# top_3-28-21.net
KiCad netlist of a schematic drawn in EAGLE
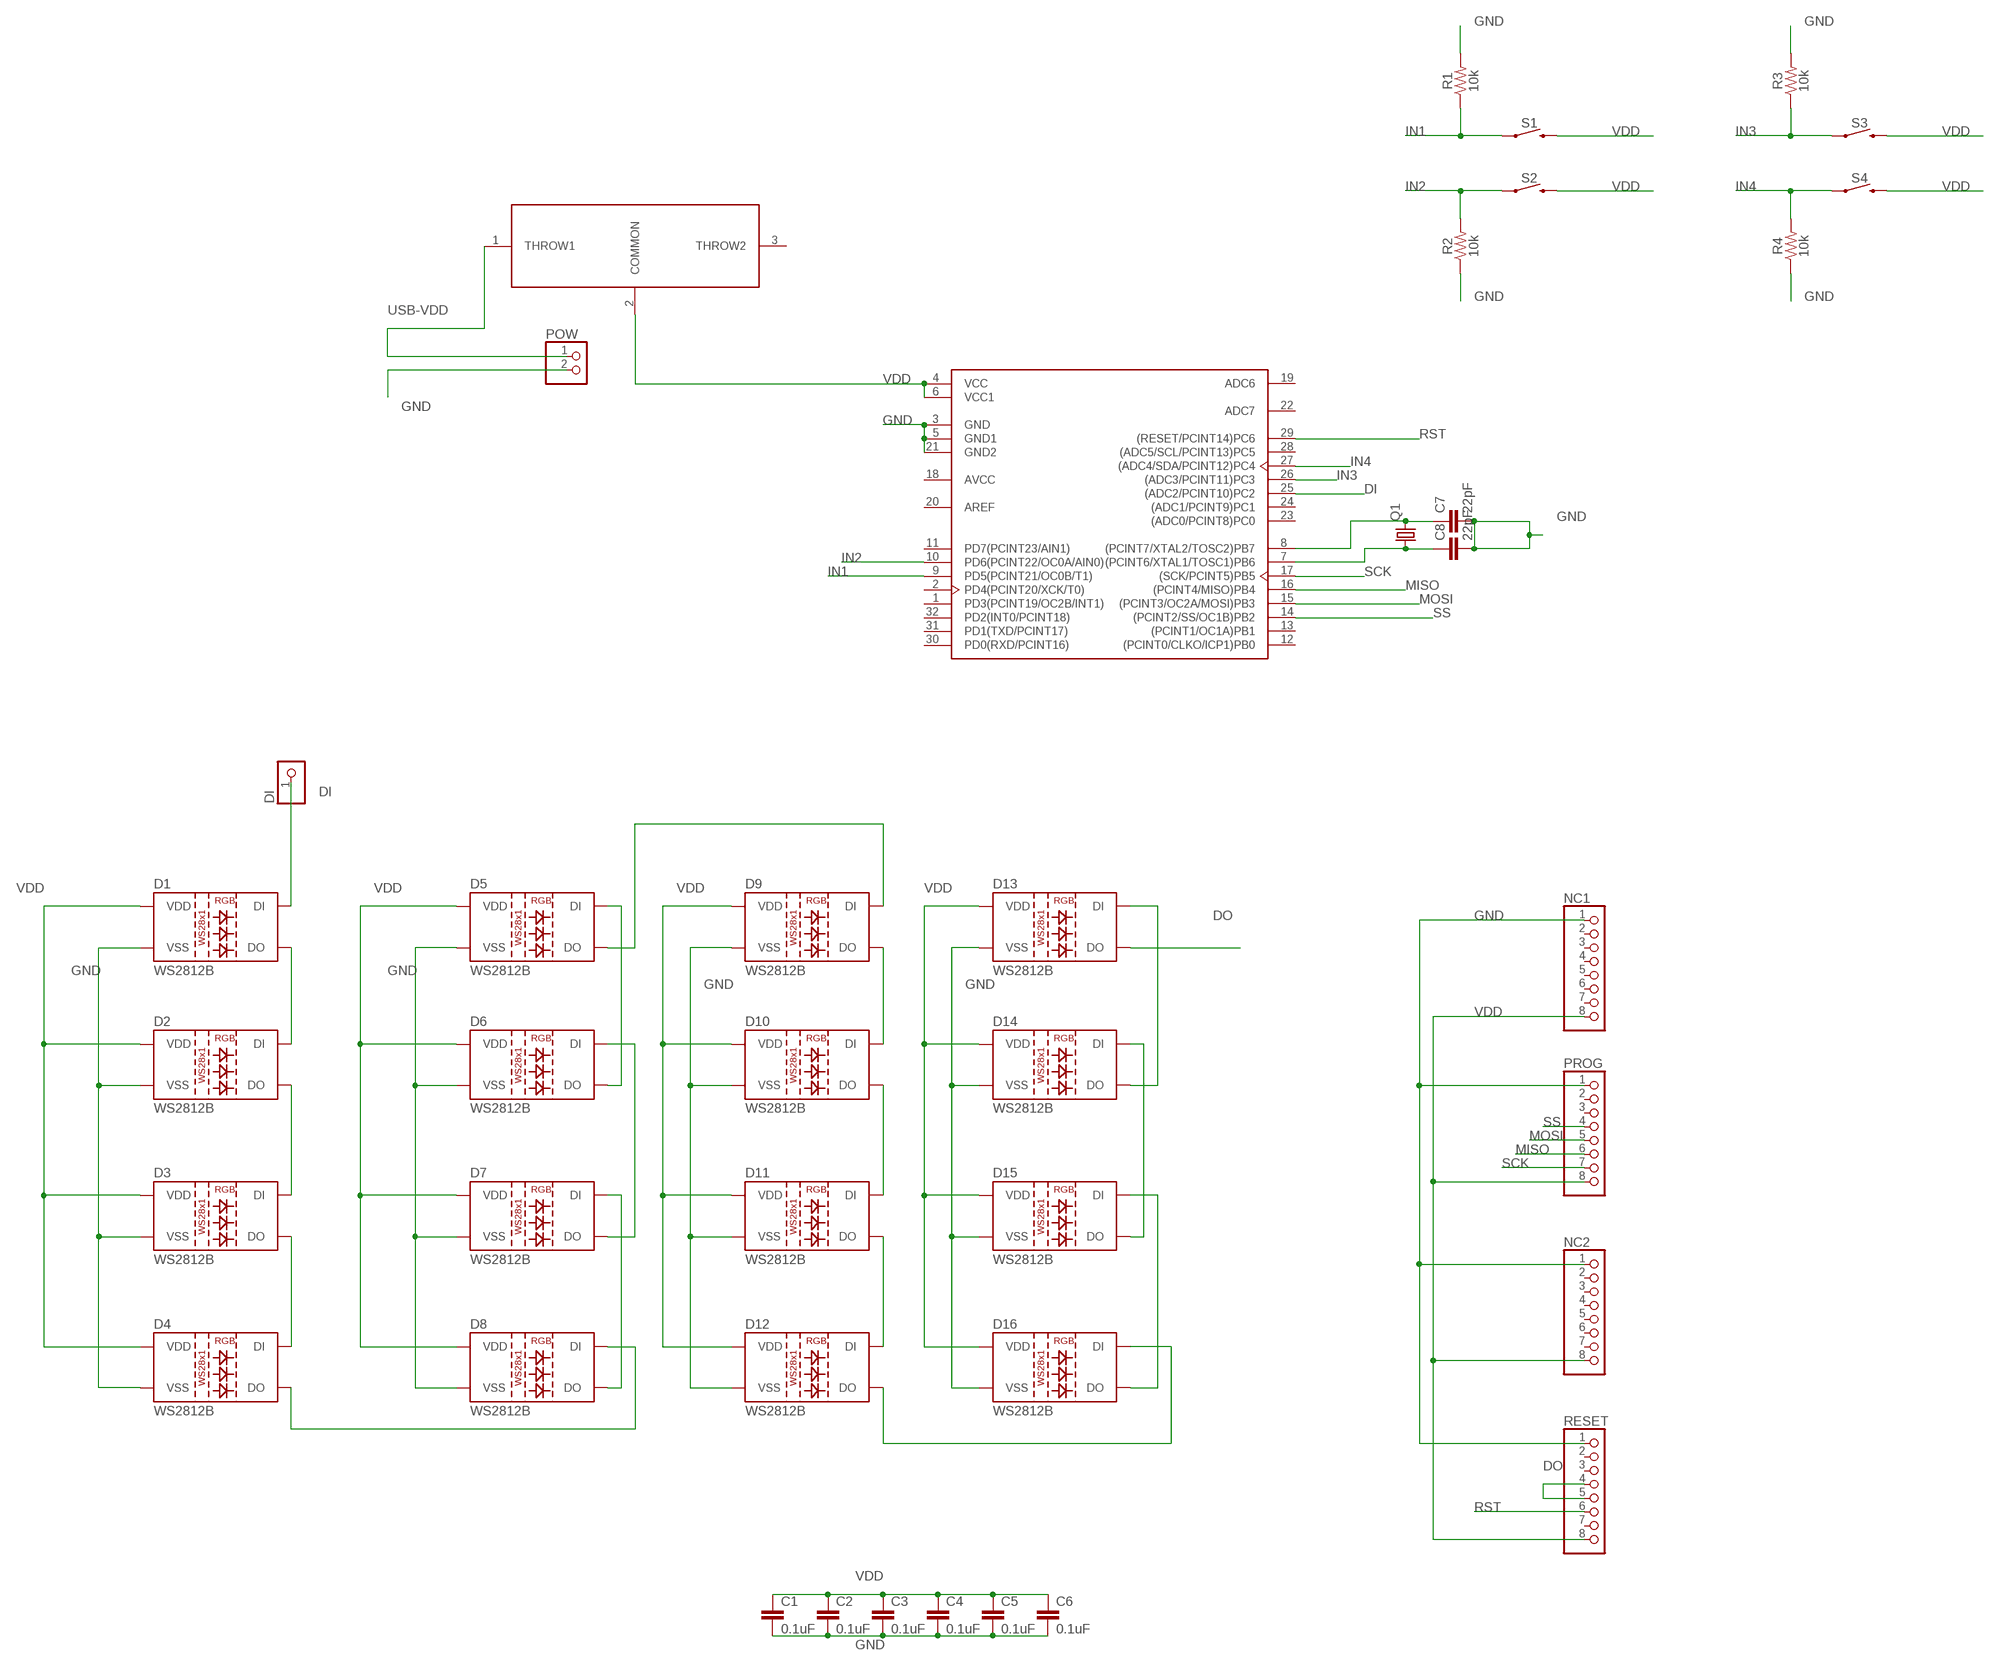
[diagram p0: schematic, sheet 1]

(export (version "E")
  (design (tool "Eeschema 10.0.6"))
  (components
    (comp (ref "C1")
      (value "0.1uF")
      (footprint "eagle-import:0603")
      (libsource (lib "eagle-import") (part "0.1UF-0603-25V-5%"))
    )
    (comp (ref "C2")
      (value "0.1uF")
      (footprint "eagle-import:0603")
      (libsource (lib "eagle-import") (part "0.1UF-0603-25V-5%"))
    )
    (comp (ref "C3")
      (value "0.1uF")
      (footprint "eagle-import:0603")
      (libsource (lib "eagle-import") (part "0.1UF-0603-25V-5%"))
    )
    (comp (ref "C4")
      (value "0.1uF")
      (footprint "eagle-import:0603")
      (libsource (lib "eagle-import") (part "0.1UF-0603-25V-5%"))
    )
    (comp (ref "C5")
      (value "0.1uF")
      (footprint "eagle-import:0603")
      (libsource (lib "eagle-import") (part "0.1UF-0603-25V-5%"))
    )
    (comp (ref "C6")
      (value "0.1uF")
      (footprint "eagle-import:0603")
      (libsource (lib "eagle-import") (part "0.1UF-0603-25V-5%"))
    )
    (comp (ref "C7")
      (value "22pF")
      (footprint "eagle-import:0805")
      (libsource (lib "eagle-import") (part "1.0UF-0805-25V-(+80/-20%)"))
    )
    (comp (ref "C8")
      (value "22pF")
      (footprint "eagle-import:0805")
      (libsource (lib "eagle-import") (part "1.0UF-0805-25V-(+80/-20%)"))
    )
    (comp (ref "D1")
      (value "WS2812B")
      (footprint "eagle-import:WS2812B")
      (libsource (lib "eagle-import") (part "WS2812B"))
    )
    (comp (ref "D2")
      (value "WS2812B")
      (footprint "eagle-import:WS2812B")
      (libsource (lib "eagle-import") (part "WS2812B"))
    )
    (comp (ref "D3")
      (value "WS2812B")
      (footprint "eagle-import:WS2812B")
      (libsource (lib "eagle-import") (part "WS2812B"))
    )
    (comp (ref "D4")
      (value "WS2812B")
      (footprint "eagle-import:WS2812B")
      (libsource (lib "eagle-import") (part "WS2812B"))
    )
    (comp (ref "D5")
      (value "WS2812B")
      (footprint "eagle-import:WS2812B")
      (libsource (lib "eagle-import") (part "WS2812B"))
    )
    (comp (ref "D6")
      (value "WS2812B")
      (footprint "eagle-import:WS2812B")
      (libsource (lib "eagle-import") (part "WS2812B"))
    )
    (comp (ref "D7")
      (value "WS2812B")
      (footprint "eagle-import:WS2812B")
      (libsource (lib "eagle-import") (part "WS2812B"))
    )
    (comp (ref "D8")
      (value "WS2812B")
      (footprint "eagle-import:WS2812B")
      (libsource (lib "eagle-import") (part "WS2812B"))
    )
    (comp (ref "D9")
      (value "WS2812B")
      (footprint "eagle-import:WS2812B")
      (libsource (lib "eagle-import") (part "WS2812B"))
    )
    (comp (ref "D10")
      (value "WS2812B")
      (footprint "eagle-import:WS2812B")
      (libsource (lib "eagle-import") (part "WS2812B"))
    )
    (comp (ref "D11")
      (value "WS2812B")
      (footprint "eagle-import:WS2812B")
      (libsource (lib "eagle-import") (part "WS2812B"))
    )
    (comp (ref "D12")
      (value "WS2812B")
      (footprint "eagle-import:WS2812B")
      (libsource (lib "eagle-import") (part "WS2812B"))
    )
    (comp (ref "D13")
      (value "WS2812B")
      (footprint "eagle-import:WS2812B")
      (libsource (lib "eagle-import") (part "WS2812B"))
    )
    (comp (ref "D14")
      (value "WS2812B")
      (footprint "eagle-import:WS2812B")
      (libsource (lib "eagle-import") (part "WS2812B"))
    )
    (comp (ref "D15")
      (value "WS2812B")
      (footprint "eagle-import:WS2812B")
      (libsource (lib "eagle-import") (part "WS2812B"))
    )
    (comp (ref "D16")
      (value "WS2812B")
      (footprint "eagle-import:WS2812B")
      (libsource (lib "eagle-import") (part "WS2812B"))
    )
    (comp (ref "DI")
      (value "PINHD-1X1")
      (footprint "eagle-import:1X01")
      (libsource (lib "eagle-import") (part "PINHD-1X1"))
    )
    (comp (ref "IC1")
      (value "ATMEGA328P-AU")
      (footprint "eagle-import:TQFP-32")
      (fields
        (field (name "DIGIKEY_PART_NUMBER") "ATMEGA328P-AU-ND")
        (field (name "MANUFACTURER") "Microchip Technology")
        (field (name "CREATED_BY") "PCBLayout.com")
      )
      (libsource (lib "eagle-import") (part "ATMEGA328P-AU"))
    )
    (comp (ref "NC1")
      (value "PINHD-1X8")
      (footprint "eagle-import:1X08")
      (libsource (lib "eagle-import") (part "PINHD-1X8"))
    )
    (comp (ref "NC2")
      (value "PINHD-1X8")
      (footprint "eagle-import:1X08")
      (libsource (lib "eagle-import") (part "PINHD-1X8"))
    )
    (comp (ref "POW")
      (value "PINHD-1X2")
      (footprint "eagle-import:1X02")
      (libsource (lib "eagle-import") (part "PINHD-1X2"))
    )
    (comp (ref "PROG")
      (value "PINHD-1X8")
      (footprint "eagle-import:1X08")
      (libsource (lib "eagle-import") (part "PINHD-1X8"))
    )
    (comp (ref "Q1")
      (value "CRYSTALHC49S")
      (footprint "eagle-import:HC49_S")
      (libsource (lib "eagle-import") (part "CRYSTALHC49S"))
    )
    (comp (ref "R1")
      (value "10k")
      (footprint "eagle-import:0805")
      (libsource (lib "eagle-import") (part "0.3OHM-0805-1/8W-1%"))
    )
    (comp (ref "R2")
      (value "10k")
      (footprint "eagle-import:0805")
      (libsource (lib "eagle-import") (part "0.3OHM-0805-1/8W-1%"))
    )
    (comp (ref "R3")
      (value "10k")
      (footprint "eagle-import:0805")
      (libsource (lib "eagle-import") (part "0.3OHM-0805-1/8W-1%"))
    )
    (comp (ref "R4")
      (value "10k")
      (footprint "eagle-import:0805")
      (libsource (lib "eagle-import") (part "0.3OHM-0805-1/8W-1%"))
    )
    (comp (ref "RESET")
      (value "PINHD-1X8")
      (footprint "eagle-import:1X08")
      (libsource (lib "eagle-import") (part "PINHD-1X8"))
    )
    (comp (ref "S1")
      (value "MOMENTARY-SWITCH-SPST-PTH-6.0MM")
      (footprint "eagle-import:TACTILE_SWITCH_PTH_6.0MM")
      (libsource (lib "eagle-import") (part "MOMENTARY-SWITCH-SPST-PTH-6.0MM"))
    )
    (comp (ref "S2")
      (value "MOMENTARY-SWITCH-SPST-PTH-6.0MM")
      (footprint "eagle-import:TACTILE_SWITCH_PTH_6.0MM")
      (libsource (lib "eagle-import") (part "MOMENTARY-SWITCH-SPST-PTH-6.0MM"))
    )
    (comp (ref "S3")
      (value "MOMENTARY-SWITCH-SPST-PTH-6.0MM")
      (footprint "eagle-import:TACTILE_SWITCH_PTH_6.0MM")
      (libsource (lib "eagle-import") (part "MOMENTARY-SWITCH-SPST-PTH-6.0MM"))
    )
    (comp (ref "S4")
      (value "MOMENTARY-SWITCH-SPST-PTH-6.0MM")
      (footprint "eagle-import:TACTILE_SWITCH_PTH_6.0MM")
      (libsource (lib "eagle-import") (part "MOMENTARY-SWITCH-SPST-PTH-6.0MM"))
    )
    (comp (ref "U$2")
      (value "SLIDE_SWITCH_1P2T")
      (footprint "eagle-import:SLIDE_SWITCH_1P2T")
      (libsource (lib "eagle-import") (part "SLIDE_SWITCH_1P2T"))
    )
  )
  (nets
    (net (code "1") (name "/AREF") (class "Default")
      (node (ref "IC1") (pin "20") (pinfunction "AREF_20") (pintype "power_in"))
    )
    (net (code "2") (name "/AVCC") (class "Default")
      (node (ref "IC1") (pin "18") (pinfunction "AVCC_18") (pintype "power_in"))
    )
    (net (code "3") (name "/DI") (class "Default")
      (node (ref "D1") (pin "4") (pinfunction "DI_4") (pintype "bidirectional"))
      (node (ref "DI") (pin "1") (pinfunction "1_1") (pintype "passive"))
      (node (ref "IC1") (pin "25") (pinfunction "(ADC2/PCINT10)PC2_25") (pintype "bidirectional"))
    )
    (net (code "4") (name "/DO") (class "Default")
      (node (ref "D13") (pin "2") (pinfunction "DO_2") (pintype "bidirectional"))
      (node (ref "RESET") (pin "4") (pinfunction "4_4") (pintype "passive"))
      (node (ref "RESET") (pin "5") (pinfunction "5_5") (pintype "passive"))
    )
    (net (code "5") (name "/GND") (class "Default")
      (node (ref "C1") (pin "2") (pinfunction "2_2") (pintype "passive"))
      (node (ref "C2") (pin "2") (pinfunction "2_2") (pintype "passive"))
      (node (ref "C3") (pin "2") (pinfunction "2_2") (pintype "passive"))
      (node (ref "C4") (pin "2") (pinfunction "2_2") (pintype "passive"))
      (node (ref "C5") (pin "2") (pinfunction "2_2") (pintype "passive"))
      (node (ref "C6") (pin "2") (pinfunction "2_2") (pintype "passive"))
      (node (ref "C7") (pin "2") (pinfunction "2_2") (pintype "passive"))
      (node (ref "C8") (pin "2") (pinfunction "2_2") (pintype "passive"))
      (node (ref "D1") (pin "3") (pinfunction "VSS_3") (pintype "bidirectional"))
      (node (ref "D10") (pin "3") (pinfunction "VSS_3") (pintype "bidirectional"))
      (node (ref "D11") (pin "3") (pinfunction "VSS_3") (pintype "bidirectional"))
      (node (ref "D12") (pin "3") (pinfunction "VSS_3") (pintype "bidirectional"))
      (node (ref "D13") (pin "3") (pinfunction "VSS_3") (pintype "bidirectional"))
      (node (ref "D14") (pin "3") (pinfunction "VSS_3") (pintype "bidirectional"))
      (node (ref "D15") (pin "3") (pinfunction "VSS_3") (pintype "bidirectional"))
      (node (ref "D16") (pin "3") (pinfunction "VSS_3") (pintype "bidirectional"))
      (node (ref "D2") (pin "3") (pinfunction "VSS_3") (pintype "bidirectional"))
      (node (ref "D3") (pin "3") (pinfunction "VSS_3") (pintype "bidirectional"))
      (node (ref "D4") (pin "3") (pinfunction "VSS_3") (pintype "bidirectional"))
      (node (ref "D5") (pin "3") (pinfunction "VSS_3") (pintype "bidirectional"))
      (node (ref "D6") (pin "3") (pinfunction "VSS_3") (pintype "bidirectional"))
      (node (ref "D7") (pin "3") (pinfunction "VSS_3") (pintype "bidirectional"))
      (node (ref "D8") (pin "3") (pinfunction "VSS_3") (pintype "bidirectional"))
      (node (ref "D9") (pin "3") (pinfunction "VSS_3") (pintype "bidirectional"))
      (node (ref "IC1") (pin "21") (pinfunction "GND2_21") (pintype "power_in"))
      (node (ref "IC1") (pin "3") (pinfunction "GND_3") (pintype "power_in"))
      (node (ref "IC1") (pin "5") (pinfunction "GND1_5") (pintype "power_in"))
      (node (ref "NC1") (pin "1") (pinfunction "1_1") (pintype "passive"))
      (node (ref "NC2") (pin "1") (pinfunction "1_1") (pintype "passive"))
      (node (ref "POW") (pin "2") (pinfunction "2_2") (pintype "passive"))
      (node (ref "PROG") (pin "1") (pinfunction "1_1") (pintype "passive"))
      (node (ref "R1") (pin "2") (pinfunction "2_2") (pintype "passive"))
      (node (ref "R2") (pin "1") (pinfunction "1_1") (pintype "passive"))
      (node (ref "R3") (pin "2") (pinfunction "2_2") (pintype "passive"))
      (node (ref "R4") (pin "1") (pinfunction "1_1") (pintype "passive"))
      (node (ref "RESET") (pin "1") (pinfunction "1_1") (pintype "passive"))
    )
    (net (code "6") (name "/IN1") (class "Default")
      (node (ref "IC1") (pin "9") (pinfunction "PD5(PCINT21/OC0B/T1)_9") (pintype "bidirectional"))
      (node (ref "R1") (pin "1") (pinfunction "1_1") (pintype "passive"))
      (node (ref "S1") (pin "1") (pinfunction "1_1") (pintype "passive"))
    )
    (net (code "7") (name "/IN2") (class "Default")
      (node (ref "IC1") (pin "10") (pinfunction "PD6(PCINT22/OC0A/AIN0)_10") (pintype "bidirectional"))
      (node (ref "R2") (pin "2") (pinfunction "2_2") (pintype "passive"))
      (node (ref "S2") (pin "1") (pinfunction "1_1") (pintype "passive"))
    )
    (net (code "8") (name "/IN3") (class "Default")
      (node (ref "IC1") (pin "26") (pinfunction "(ADC3/PCINT11)PC3_26") (pintype "bidirectional"))
      (node (ref "R3") (pin "1") (pinfunction "1_1") (pintype "passive"))
      (node (ref "S3") (pin "1") (pinfunction "1_1") (pintype "passive"))
    )
    (net (code "9") (name "/IN4") (class "Default")
      (node (ref "IC1") (pin "27") (pinfunction "(ADC4/SDA/PCINT12)PC4_27") (pintype "bidirectional"))
      (node (ref "R4") (pin "2") (pinfunction "2_2") (pintype "passive"))
      (node (ref "S4") (pin "1") (pinfunction "1_1") (pintype "passive"))
    )
    (net (code "10") (name "/MISO") (class "Default")
      (node (ref "IC1") (pin "16") (pinfunction "(PCINT4/MISO)PB4_16") (pintype "bidirectional"))
      (node (ref "PROG") (pin "6") (pinfunction "6_6") (pintype "passive"))
    )
    (net (code "11") (name "/MOSI") (class "Default")
      (node (ref "IC1") (pin "15") (pinfunction "(PCINT3/OC2A/MOSI)PB3_15") (pintype "bidirectional"))
      (node (ref "PROG") (pin "5") (pinfunction "5_5") (pintype "passive"))
    )
    (net (code "12") (name "/RST") (class "Default")
      (node (ref "IC1") (pin "29") (pinfunction "(RESET/PCINT14)PC6_29") (pintype "bidirectional"))
      (node (ref "RESET") (pin "6") (pinfunction "6_6") (pintype "passive"))
    )
    (net (code "13") (name "/SCK") (class "Default")
      (node (ref "IC1") (pin "17") (pinfunction "(SCK/PCINT5)PB5_17") (pintype "bidirectional"))
      (node (ref "PROG") (pin "7") (pinfunction "7_7") (pintype "passive"))
    )
    (net (code "14") (name "/SS") (class "Default")
      (node (ref "IC1") (pin "14") (pinfunction "(PCINT2/SS/OC1B)PB2_14") (pintype "bidirectional"))
      (node (ref "PROG") (pin "4") (pinfunction "4_4") (pintype "passive"))
    )
    (net (code "15") (name "/USB-VDD") (class "Default")
      (node (ref "POW") (pin "1") (pinfunction "1_1") (pintype "passive"))
      (node (ref "U$2") (pin "1") (pinfunction "THROW1_1") (pintype "bidirectional"))
    )
    (net (code "16") (name "/VDD") (class "Default")
      (node (ref "C1") (pin "1") (pinfunction "1_1") (pintype "passive"))
      (node (ref "C2") (pin "1") (pinfunction "1_1") (pintype "passive"))
      (node (ref "C3") (pin "1") (pinfunction "1_1") (pintype "passive"))
      (node (ref "C4") (pin "1") (pinfunction "1_1") (pintype "passive"))
      (node (ref "C5") (pin "1") (pinfunction "1_1") (pintype "passive"))
      (node (ref "C6") (pin "1") (pinfunction "1_1") (pintype "passive"))
      (node (ref "D1") (pin "1") (pinfunction "VDD_1") (pintype "bidirectional"))
      (node (ref "D10") (pin "1") (pinfunction "VDD_1") (pintype "bidirectional"))
      (node (ref "D11") (pin "1") (pinfunction "VDD_1") (pintype "bidirectional"))
      (node (ref "D12") (pin "1") (pinfunction "VDD_1") (pintype "bidirectional"))
      (node (ref "D13") (pin "1") (pinfunction "VDD_1") (pintype "bidirectional"))
      (node (ref "D14") (pin "1") (pinfunction "VDD_1") (pintype "bidirectional"))
      (node (ref "D15") (pin "1") (pinfunction "VDD_1") (pintype "bidirectional"))
      (node (ref "D16") (pin "1") (pinfunction "VDD_1") (pintype "bidirectional"))
      (node (ref "D2") (pin "1") (pinfunction "VDD_1") (pintype "bidirectional"))
      (node (ref "D3") (pin "1") (pinfunction "VDD_1") (pintype "bidirectional"))
      (node (ref "D4") (pin "1") (pinfunction "VDD_1") (pintype "bidirectional"))
      (node (ref "D5") (pin "1") (pinfunction "VDD_1") (pintype "bidirectional"))
      (node (ref "D6") (pin "1") (pinfunction "VDD_1") (pintype "bidirectional"))
      (node (ref "D7") (pin "1") (pinfunction "VDD_1") (pintype "bidirectional"))
      (node (ref "D8") (pin "1") (pinfunction "VDD_1") (pintype "bidirectional"))
      (node (ref "D9") (pin "1") (pinfunction "VDD_1") (pintype "bidirectional"))
      (node (ref "IC1") (pin "4") (pinfunction "VCC_4") (pintype "power_in"))
      (node (ref "IC1") (pin "6") (pinfunction "VCC1_6") (pintype "power_in"))
      (node (ref "NC1") (pin "8") (pinfunction "8_8") (pintype "passive"))
      (node (ref "NC2") (pin "8") (pinfunction "8_8") (pintype "passive"))
      (node (ref "PROG") (pin "8") (pinfunction "8_8") (pintype "passive"))
      (node (ref "RESET") (pin "8") (pinfunction "8_8") (pintype "passive"))
      (node (ref "S1") (pin "3") (pinfunction "2_3") (pintype "passive"))
      (node (ref "S2") (pin "3") (pinfunction "2_3") (pintype "passive"))
      (node (ref "S3") (pin "3") (pinfunction "2_3") (pintype "passive"))
      (node (ref "S4") (pin "3") (pinfunction "2_3") (pintype "passive"))
      (node (ref "U$2") (pin "2") (pinfunction "COMMON_2") (pintype "bidirectional"))
    )
    (net (code "17") (name "Net-(D1-DO)") (class "Default")
      (node (ref "D1") (pin "2") (pinfunction "DO_2") (pintype "bidirectional"))
      (node (ref "D2") (pin "4") (pinfunction "DI_4") (pintype "bidirectional"))
    )
    (net (code "18") (name "Net-(D2-DO)") (class "Default")
      (node (ref "D2") (pin "2") (pinfunction "DO_2") (pintype "bidirectional"))
      (node (ref "D3") (pin "4") (pinfunction "DI_4") (pintype "bidirectional"))
    )
    (net (code "19") (name "Net-(D3-DO)") (class "Default")
      (node (ref "D3") (pin "2") (pinfunction "DO_2") (pintype "bidirectional"))
      (node (ref "D4") (pin "4") (pinfunction "DI_4") (pintype "bidirectional"))
    )
    (net (code "20") (name "Net-(D4-DO)") (class "Default")
      (node (ref "D4") (pin "2") (pinfunction "DO_2") (pintype "bidirectional"))
      (node (ref "D8") (pin "4") (pinfunction "DI_4") (pintype "bidirectional"))
    )
    (net (code "21") (name "Net-(D5-DI)") (class "Default")
      (node (ref "D5") (pin "4") (pinfunction "DI_4") (pintype "bidirectional"))
      (node (ref "D6") (pin "2") (pinfunction "DO_2") (pintype "bidirectional"))
    )
    (net (code "22") (name "Net-(D5-DO)") (class "Default")
      (node (ref "D5") (pin "2") (pinfunction "DO_2") (pintype "bidirectional"))
      (node (ref "D9") (pin "4") (pinfunction "DI_4") (pintype "bidirectional"))
    )
    (net (code "23") (name "Net-(D6-DI)") (class "Default")
      (node (ref "D6") (pin "4") (pinfunction "DI_4") (pintype "bidirectional"))
      (node (ref "D7") (pin "2") (pinfunction "DO_2") (pintype "bidirectional"))
    )
    (net (code "24") (name "Net-(D7-DI)") (class "Default")
      (node (ref "D7") (pin "4") (pinfunction "DI_4") (pintype "bidirectional"))
      (node (ref "D8") (pin "2") (pinfunction "DO_2") (pintype "bidirectional"))
    )
    (net (code "25") (name "Net-(D10-DI)") (class "Default")
      (node (ref "D10") (pin "4") (pinfunction "DI_4") (pintype "bidirectional"))
      (node (ref "D9") (pin "2") (pinfunction "DO_2") (pintype "bidirectional"))
    )
    (net (code "26") (name "Net-(D10-DO)") (class "Default")
      (node (ref "D10") (pin "2") (pinfunction "DO_2") (pintype "bidirectional"))
      (node (ref "D11") (pin "4") (pinfunction "DI_4") (pintype "bidirectional"))
    )
    (net (code "27") (name "Net-(D11-DO)") (class "Default")
      (node (ref "D11") (pin "2") (pinfunction "DO_2") (pintype "bidirectional"))
      (node (ref "D12") (pin "4") (pinfunction "DI_4") (pintype "bidirectional"))
    )
    (net (code "28") (name "Net-(D12-DO)") (class "Default")
      (node (ref "D12") (pin "2") (pinfunction "DO_2") (pintype "bidirectional"))
      (node (ref "D16") (pin "4") (pinfunction "DI_4") (pintype "bidirectional"))
    )
    (net (code "29") (name "Net-(D13-DI)") (class "Default")
      (node (ref "D13") (pin "4") (pinfunction "DI_4") (pintype "bidirectional"))
      (node (ref "D14") (pin "2") (pinfunction "DO_2") (pintype "bidirectional"))
    )
    (net (code "30") (name "Net-(D14-DI)") (class "Default")
      (node (ref "D14") (pin "4") (pinfunction "DI_4") (pintype "bidirectional"))
      (node (ref "D15") (pin "2") (pinfunction "DO_2") (pintype "bidirectional"))
    )
    (net (code "31") (name "Net-(D15-DI)") (class "Default")
      (node (ref "D15") (pin "4") (pinfunction "DI_4") (pintype "bidirectional"))
      (node (ref "D16") (pin "2") (pinfunction "DO_2") (pintype "bidirectional"))
    )
    (net (code "32") (name "Net-(IC1-(PCINT6{slash}XTAL1{slash}TOSC1)PB6)") (class "Default")
      (node (ref "C8") (pin "1") (pinfunction "1_1") (pintype "passive"))
      (node (ref "IC1") (pin "7") (pinfunction "(PCINT6/XTAL1/TOSC1)PB6_7") (pintype "bidirectional"))
      (node (ref "Q1") (pin "1") (pinfunction "1_1") (pintype "passive"))
    )
    (net (code "33") (name "Net-(IC1-(PCINT7{slash}XTAL2{slash}TOSC2)PB7)") (class "Default")
      (node (ref "C7") (pin "1") (pinfunction "1_1") (pintype "passive"))
      (node (ref "IC1") (pin "8") (pinfunction "(PCINT7/XTAL2/TOSC2)PB7_8") (pintype "bidirectional"))
      (node (ref "Q1") (pin "2") (pinfunction "2_2") (pintype "passive"))
    )
    (net (code "34") (name "unconnected-(IC1-(ADC0{slash}PCINT8)PC0-Pad23)") (class "Default")
      (node (ref "IC1") (pin "23") (pinfunction "(ADC0/PCINT8)PC0_23") (pintype "bidirectional"))
    )
    (net (code "35") (name "unconnected-(IC1-(ADC1{slash}PCINT9)PC1-Pad24)") (class "Default")
      (node (ref "IC1") (pin "24") (pinfunction "(ADC1/PCINT9)PC1_24") (pintype "bidirectional"))
    )
    (net (code "36") (name "unconnected-(IC1-(ADC5{slash}SCL{slash}PCINT13)PC5-Pad28)") (class "Default")
      (node (ref "IC1") (pin "28") (pinfunction "(ADC5/SCL/PCINT13)PC5_28") (pintype "bidirectional"))
    )
    (net (code "37") (name "unconnected-(IC1-(PCINT0{slash}CLKO{slash}ICP1)PB0-Pad12)") (class "Default")
      (node (ref "IC1") (pin "12") (pinfunction "(PCINT0/CLKO/ICP1)PB0_12") (pintype "bidirectional"))
    )
    (net (code "38") (name "unconnected-(IC1-(PCINT1{slash}OC1A)PB1-Pad13)") (class "Default")
      (node (ref "IC1") (pin "13") (pinfunction "(PCINT1/OC1A)PB1_13") (pintype "bidirectional"))
    )
    (net (code "39") (name "unconnected-(IC1-ADC6-Pad19)") (class "Default")
      (node (ref "IC1") (pin "19") (pinfunction "ADC6_19") (pintype "input"))
    )
    (net (code "40") (name "unconnected-(IC1-ADC7-Pad22)") (class "Default")
      (node (ref "IC1") (pin "22") (pinfunction "ADC7_22") (pintype "input"))
    )
    (net (code "41") (name "unconnected-(IC1-PD0(RXD{slash}PCINT16)-Pad30)") (class "Default")
      (node (ref "IC1") (pin "30") (pinfunction "PD0(RXD/PCINT16)_30") (pintype "bidirectional"))
    )
    (net (code "42") (name "unconnected-(IC1-PD1(TXD{slash}PCINT17)-Pad31)") (class "Default")
      (node (ref "IC1") (pin "31") (pinfunction "PD1(TXD/PCINT17)_31") (pintype "bidirectional"))
    )
    (net (code "43") (name "unconnected-(IC1-PD2(INT0{slash}PCINT18)-Pad32)") (class "Default")
      (node (ref "IC1") (pin "32") (pinfunction "PD2(INT0/PCINT18)_32") (pintype "bidirectional"))
    )
    (net (code "44") (name "unconnected-(IC1-PD3(PCINT19{slash}OC2B{slash}INT1)-Pad1)") (class "Default")
      (node (ref "IC1") (pin "1") (pinfunction "PD3(PCINT19/OC2B/INT1)_1") (pintype "bidirectional"))
    )
    (net (code "45") (name "unconnected-(IC1-PD4(PCINT20{slash}XCK{slash}T0)-Pad2)") (class "Default")
      (node (ref "IC1") (pin "2") (pinfunction "PD4(PCINT20/XCK/T0)_2") (pintype "bidirectional"))
    )
    (net (code "46") (name "unconnected-(IC1-PD7(PCINT23{slash}AIN1)-Pad11)") (class "Default")
      (node (ref "IC1") (pin "11") (pinfunction "PD7(PCINT23/AIN1)_11") (pintype "bidirectional"))
    )
    (net (code "47") (name "unconnected-(NC1-Pad2)") (class "Default")
      (node (ref "NC1") (pin "2") (pinfunction "2_2") (pintype "passive"))
    )
    (net (code "48") (name "unconnected-(NC1-Pad3)") (class "Default")
      (node (ref "NC1") (pin "3") (pinfunction "3_3") (pintype "passive"))
    )
    (net (code "49") (name "unconnected-(NC1-Pad4)") (class "Default")
      (node (ref "NC1") (pin "4") (pinfunction "4_4") (pintype "passive"))
    )
    (net (code "50") (name "unconnected-(NC1-Pad5)") (class "Default")
      (node (ref "NC1") (pin "5") (pinfunction "5_5") (pintype "passive"))
    )
    (net (code "51") (name "unconnected-(NC1-Pad6)") (class "Default")
      (node (ref "NC1") (pin "6") (pinfunction "6_6") (pintype "passive"))
    )
    (net (code "52") (name "unconnected-(NC1-Pad7)") (class "Default")
      (node (ref "NC1") (pin "7") (pinfunction "7_7") (pintype "passive"))
    )
    (net (code "53") (name "unconnected-(NC2-Pad2)") (class "Default")
      (node (ref "NC2") (pin "2") (pinfunction "2_2") (pintype "passive"))
    )
    (net (code "54") (name "unconnected-(NC2-Pad3)") (class "Default")
      (node (ref "NC2") (pin "3") (pinfunction "3_3") (pintype "passive"))
    )
    (net (code "55") (name "unconnected-(NC2-Pad4)") (class "Default")
      (node (ref "NC2") (pin "4") (pinfunction "4_4") (pintype "passive"))
    )
    (net (code "56") (name "unconnected-(NC2-Pad5)") (class "Default")
      (node (ref "NC2") (pin "5") (pinfunction "5_5") (pintype "passive"))
    )
    (net (code "57") (name "unconnected-(NC2-Pad6)") (class "Default")
      (node (ref "NC2") (pin "6") (pinfunction "6_6") (pintype "passive"))
    )
    (net (code "58") (name "unconnected-(NC2-Pad7)") (class "Default")
      (node (ref "NC2") (pin "7") (pinfunction "7_7") (pintype "passive"))
    )
    (net (code "59") (name "unconnected-(PROG-Pad2)") (class "Default")
      (node (ref "PROG") (pin "2") (pinfunction "2_2") (pintype "passive"))
    )
    (net (code "60") (name "unconnected-(PROG-Pad3)") (class "Default")
      (node (ref "PROG") (pin "3") (pinfunction "3_3") (pintype "passive"))
    )
    (net (code "61") (name "unconnected-(RESET-Pad2)") (class "Default")
      (node (ref "RESET") (pin "2") (pinfunction "2_2") (pintype "passive"))
    )
    (net (code "62") (name "unconnected-(RESET-Pad3)") (class "Default")
      (node (ref "RESET") (pin "3") (pinfunction "3_3") (pintype "passive"))
    )
    (net (code "63") (name "unconnected-(RESET-Pad7)") (class "Default")
      (node (ref "RESET") (pin "7") (pinfunction "7_7") (pintype "passive"))
    )
    (net (code "64") (name "unconnected-(U$2-THROW2-Pad3)") (class "Default")
      (node (ref "U$2") (pin "3") (pinfunction "THROW2_3") (pintype "bidirectional"))
    )
  )
)
